# MAPLE_CDH_Periph.net
KiCad netlist of a schematic drawn in Altium Designer
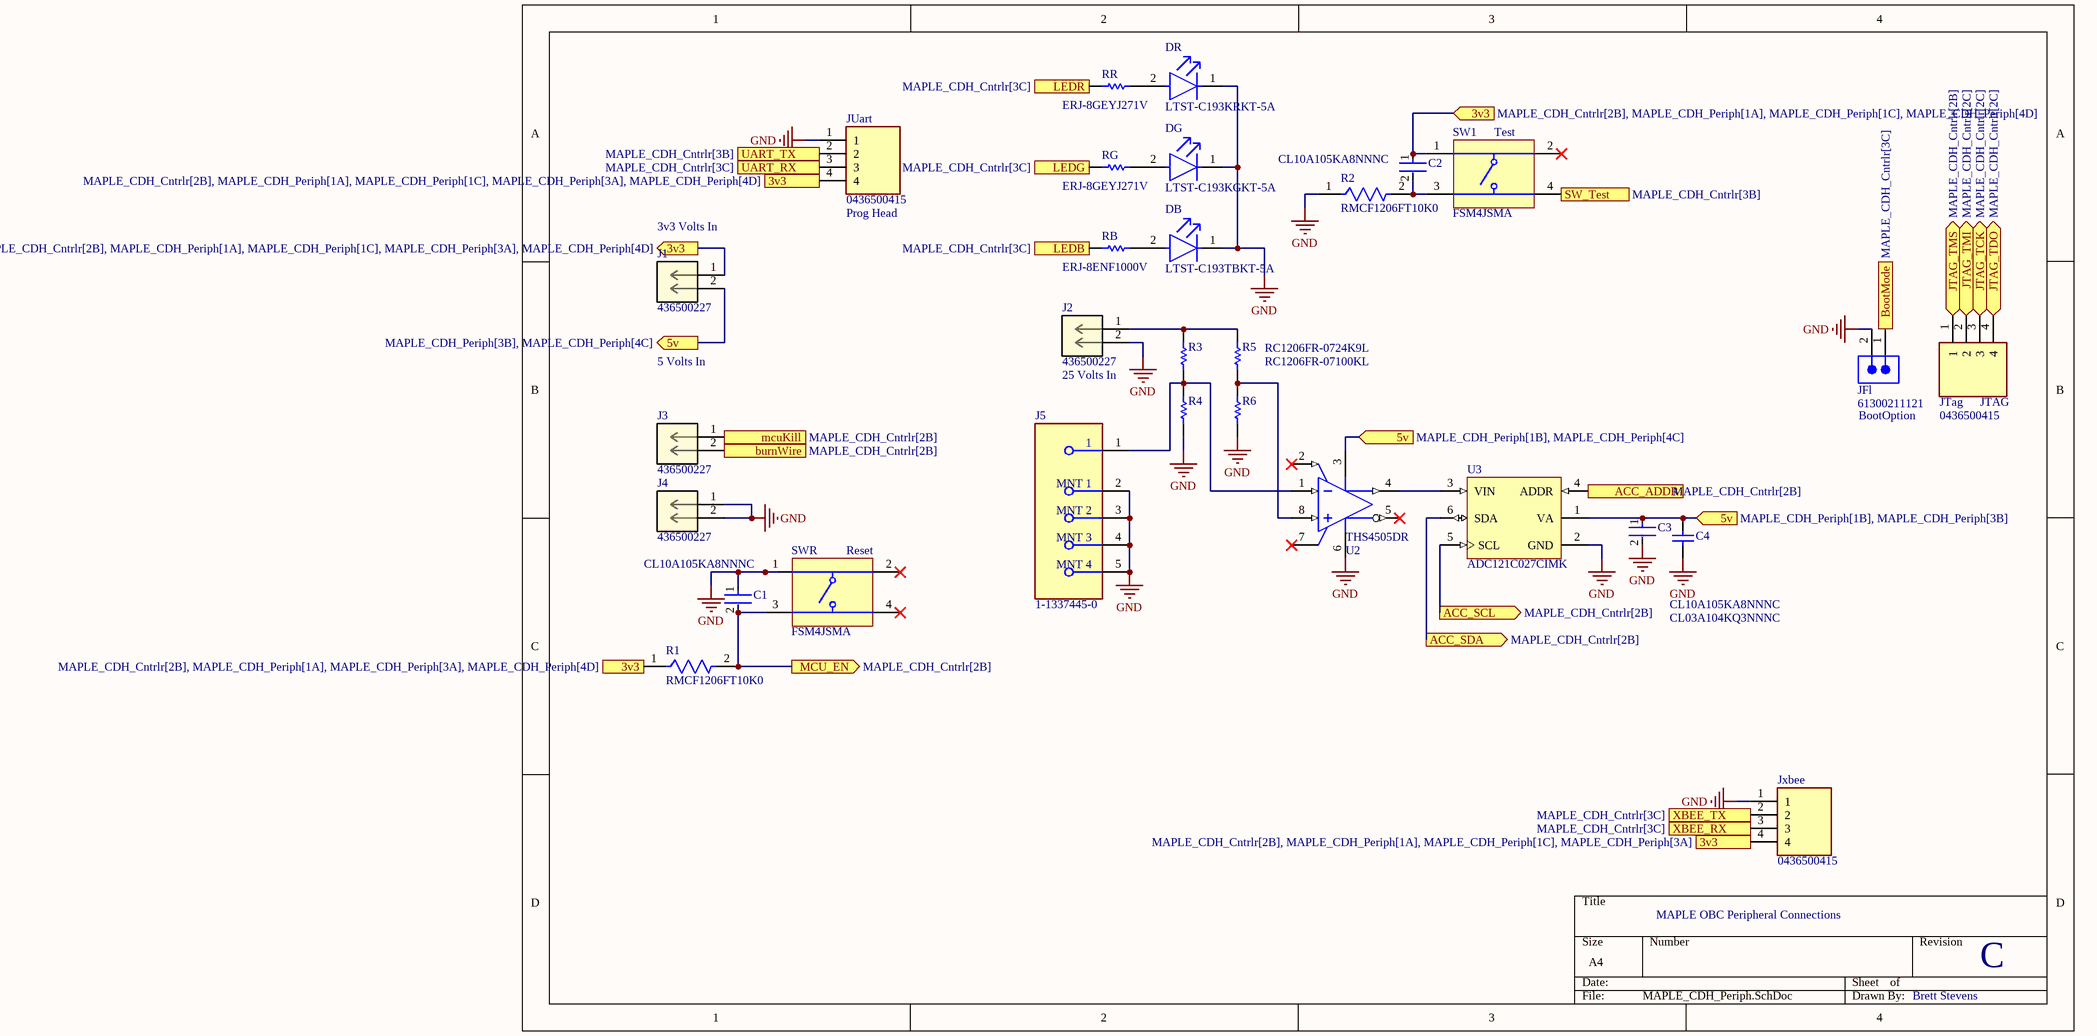
[diagram p0: MAPLE_CDH_Periph.SchDoc]

(export (version "E")
  (design (tool "Eeschema 10.0.6"))
  (components
    (comp (ref "C1")
      (value "CL10A105KA8NNNC")
      (footprint "FP-CL10-IPC_C")
      (description "Cap Ceramic 1uF 25V X5R ±10% Pad SMD 0603 +85°C T/R")
      (fields (field (name "VOLTAGE") "25V") (field (name "TOLERANCE") "10%"))
      (libsource (lib "Altium Content Vault") (part "b4654b650e69147ec39a6b967a45e02"))
    )
    (comp (ref "C2")
      (value "CL10A105KA8NNNC")
      (footprint "FP-CL10-IPC_C")
      (description "Cap Ceramic 1uF 25V X5R ±10% Pad SMD 0603 +85°C T/R")
      (fields (field (name "VOLTAGE") "25V") (field (name "TOLERANCE") "10%"))
      (libsource (lib "Altium Content Vault") (part "b4654b650e69147ec39a6b967a45e02"))
    )
    (comp (ref "C3")
      (value "CL10A105KA8NNNC")
      (footprint "FP-CL10-IPC_C")
      (description "Cap Ceramic 1uF 25V X5R ±10% Pad SMD 0603 +85°C T/R")
      (fields (field (name "VOLTAGE") "25V") (field (name "TOLERANCE") "10%"))
      (libsource (lib "Altium Content Vault") (part "b4654b650e69147ec39a6b967a45e02"))
    )
    (comp (ref "C4")
      (value "CL03A104KQ3NNNC")
      (footprint "CAPC0603X33X15ML03T05")
      (fields (field (name "MANUFACTURER") "Samsung"))
      (libsource (lib "Altium Content Vault") (part "CAP"))
    )
    (comp (ref "DB")
      (value "LTST-C193TBKT-5A")
      (footprint "FP-LTST-C193TBKT-5A-MFG")
      (description "LED BLUE CLEAR CHIP SMD")
      (libsource (lib "Altium Content Vault") (part "8706943c75ba83719d021d2fdc84c58"))
    )
    (comp (ref "DG")
      (value "LTST-C193KGKT-5A")
      (footprint "FP-LTST-C193KGKT-5A-MFG")
      (description "LED GREEN CLEAR CHIP SMD")
      (libsource (lib "Altium Content Vault") (part "8706943c75ba83719d021d2fdc84c58"))
    )
    (comp (ref "DR")
      (value "LTST-C193KRKT-5A")
      (footprint "FP-LTST-C193KRKT-5A-MFG")
      (description "LED RED CLEAR CHIP SMD")
      (libsource (lib "Altium Content Vault") (part "8706943c75ba83719d021d2fdc84c58"))
    )
    (comp (ref "J1")
      (value "436500227")
      (footprint "436500227:CON_436500227_MOL")
      (description "No Description Available")
      (fields (field (name "COPYRIGHT") "Copyright (C) 2023 Ultra Librarian. All rights reserved."))
      (libsource (lib "436500227") (part "436500227"))
    )
    (comp (ref "J2")
      (value "436500227")
      (footprint "436500227:CON_436500227_MOL")
      (description "No Description Available")
      (fields (field (name "COPYRIGHT") "Copyright (C) 2023 Ultra Librarian. All rights reserved."))
      (libsource (lib "436500227") (part "436500227"))
    )
    (comp (ref "J3")
      (value "436500227")
      (footprint "436500227:CON_436500227_MOL")
      (description "No Description Available")
      (fields (field (name "COPYRIGHT") "Copyright (C) 2023 Ultra Librarian. All rights reserved."))
      (libsource (lib "436500227") (part "436500227"))
    )
    (comp (ref "J4")
      (value "436500227")
      (footprint "436500227:CON_436500227_MOL")
      (description "No Description Available")
      (fields (field (name "COPYRIGHT") "Copyright (C) 2023 Ultra Librarian. All rights reserved."))
      (libsource (lib "436500227") (part "436500227"))
    )
    (comp (ref "J5")
      (value "1-1337445-0")
      (footprint "FP-1-1337445-0-MFG")
      (description "CONN BNC JACK STR 50 OHM PCB")
      (libsource (lib "Altium Content Vault") (part "c65b8a639cdaef1819ea20b5466f8fa"))
    )
    (comp (ref "JFl")
      (value "61300211121")
      (footprint "61300211121")
      (libsource (lib "Altium Content Vault") (part "Header_Male_1R_02P"))
    )
    (comp (ref "JTag")
      (value "0436500415")
      (footprint "MOLEX_0436500415")
      (description "Connector Header Through Hole 4 position 0.118 (3.00mm)")
      (fields (field (name "MF") "Molex"))
      (libsource (lib "") (part "0436500415_1"))
    )
    (comp (ref "JUart")
      (value "0436500415")
      (footprint "MOLEX_0436500415")
      (description "Connector Header Through Hole 4 position 0.118 (3.00mm)")
      (fields (field (name "MF") "Molex"))
      (libsource (lib "0436500415") (part "0436500415"))
    )
    (comp (ref "Jxbee")
      (value "0436500415")
      (footprint "MOLEX_0436500415")
      (description "Connector Header Through Hole 4 position 0.118 (3.00mm)")
      (fields (field (name "MF") "Molex"))
      (libsource (lib "0436500415") (part "0436500415"))
    )
    (comp (ref "R1")
      (value "RMCF1206FT10K0")
      (footprint "FP-RMCF1206-IPC_B")
      (description "10kΩ ±1% 0.25W 1206 Thick Film Chip Resistor AEC-Q200 compliant")
      (fields (field (name "TOLERANCE") "1%"))
      (libsource (lib "Altium Content Vault") (part "1029c3af85768c4190bb7ad29bc67b5"))
    )
    (comp (ref "R2")
      (value "RMCF1206FT10K0")
      (footprint "FP-RMCF1206-IPC_B")
      (description "10kΩ ±1% 0.25W 1206 Thick Film Chip Resistor AEC-Q200 compliant")
      (fields (field (name "TOLERANCE") "1%"))
      (libsource (lib "Altium Content Vault") (part "1029c3af85768c4190bb7ad29bc67b5"))
    )
    (comp (ref "R3")
      (value "~")
      (footprint "RESC3116X65X40NL10T20")
      (fields (field (name "MANUFACTURER") "Yageo") (field (name "PART NUMBER") "RC1206FR-0724K9L"))
      (libsource (lib "Altium Content Vault") (part "RES"))
    )
    (comp (ref "R4")
      (value "~")
      (footprint "RESC3116X65X40ML10T20")
      (description "Chip Resistor, 100 KOhm, +/- 1%, 0.25 W, -55 to 155 degC, 1206 (3216 Metric), RoHS, Tape and Reel")
      (fields (field (name "TOLERANCE") "1%") (field (name "MANUFACTURER") "Yageo"))
      (libsource (lib "Altium Content Vault") (part "RES-2"))
    )
    (comp (ref "R5")
      (value "RC1206FR-0724K9L")
      (footprint "RESC3116X65X40NL10T20")
      (fields (field (name "MANUFACTURER") "Yageo"))
      (libsource (lib "Altium Content Vault") (part "RES"))
    )
    (comp (ref "R6")
      (value "RC1206FR-07100KL")
      (footprint "RESC3116X65X40ML10T20")
      (description "Chip Resistor, 100 KOhm, +/- 1%, 0.25 W, -55 to 155 degC, 1206 (3216 Metric), RoHS, Tape and Reel")
      (fields (field (name "TOLERANCE") "1%") (field (name "MANUFACTURER") "Yageo"))
      (libsource (lib "Altium Content Vault") (part "RES-2"))
    )
    (comp (ref "RB")
      (value "ERJ-8ENF1000V")
      (footprint "RESC3216X70X50NL05T20")
      (fields (field (name "MANUFACTURER") "Panasonic"))
      (libsource (lib "Altium Content Vault") (part "RES"))
    )
    (comp (ref "RG")
      (value "ERJ-8GEYJ271V")
      (footprint "RESC3216X70X50NL05T20")
      (fields (field (name "MANUFACTURER") "Panasonic"))
      (libsource (lib "Altium Content Vault") (part "RES"))
    )
    (comp (ref "RR")
      (value "ERJ-8GEYJ271V")
      (footprint "RESC3216X70X50NL05T20")
      (fields (field (name "MANUFACTURER") "Panasonic"))
      (libsource (lib "Altium Content Vault") (part "RES"))
    )
    (comp (ref "SW1")
      (value "FSM4JSMA")
      (footprint "TECO-FSM4JSMA_V")
      (description "Swicth, SPST, 24 V, -35 to 85 degC, 4-Pin SMD, RoHS, Tape and Reel")
      (fields (field (name "MANUFACTURER") "TE Connectivity"))
      (libsource (lib "Altium Content Vault") (part "SW-SPST-4_A"))
    )
    (comp (ref "SWR")
      (value "FSM4JSMA")
      (footprint "TECO-FSM4JSMA_V")
      (description "Swicth, SPST, 24 V, -35 to 85 degC, 4-Pin SMD, RoHS, Tape and Reel")
      (fields (field (name "MANUFACTURER") "TE Connectivity"))
      (libsource (lib "Altium Content Vault") (part "SW-SPST-4_A"))
    )
    (comp (ref "U2")
      (value "THS4505DR")
      (footprint "D0008A_L")
      (fields (field (name "MANUFACTURER") "Texas Instruments"))
      (libsource (lib "Altium Content Vault") (part "TI-THS450XD_DGK8"))
    )
    (comp (ref "U3")
      (value "ADC121C027CIMK")
      (footprint "MK06A_N")
      (description "I2C-Compatible, 12-Bit Analog-to-Digital Converter with Alert Function, 6-pin Tiny SOT23")
      (fields (field (name "MANUFACTURER") "National Semiconductor"))
      (libsource (lib "Altium Content Vault") (part "CON-ADC-ADC101C027CIMK"))
    )
  )
  (nets
    (net (code "1") (name "/3v3") (class "Default")
      (node (ref "C2") (pin "1") (pinfunction "1_1") (pintype "passive"))
      (node (ref "J1") (pin "1") (pinfunction "1_1") (pintype "passive"))
      (node (ref "JUart") (pin "4") (pinfunction "4_4") (pintype "passive"))
      (node (ref "Jxbee") (pin "4") (pinfunction "4_4") (pintype "passive"))
      (node (ref "R1") (pin "1") (pinfunction "1_1") (pintype "passive"))
      (node (ref "SW1") (pin "1") (pinfunction "1_1") (pintype "passive"))
    )
    (net (code "2") (name "/5v") (class "Default")
      (node (ref "C3") (pin "1") (pinfunction "1_1") (pintype "passive"))
      (node (ref "C4") (pin "2") (pinfunction "2_2") (pintype "passive"))
      (node (ref "J1") (pin "2") (pinfunction "2_2") (pintype "passive"))
      (node (ref "U2") (pin "3") (pinfunction "VS+_3") (pintype "power_in"))
      (node (ref "U3") (pin "1") (pinfunction "VA_1") (pintype "power_in"))
    )
    (net (code "3") (name "/ACC_ADDR") (class "Default")
      (node (ref "U3") (pin "4") (pinfunction "ADDR_4") (pintype "input"))
    )
    (net (code "4") (name "/ACC_SCL") (class "Default")
      (node (ref "U3") (pin "5") (pinfunction "SCL_5") (pintype "input"))
    )
    (net (code "5") (name "/ACC_SDA") (class "Default")
      (node (ref "U3") (pin "6") (pinfunction "SDA_6") (pintype "bidirectional"))
    )
    (net (code "6") (name "/BootMode") (class "Default")
      (node (ref "JFl") (pin "1") (pinfunction "1_1") (pintype "passive"))
    )
    (net (code "7") (name "/JTAG_TCK") (class "Default")
      (node (ref "JTag") (pin "3") (pinfunction "3_3") (pintype "passive"))
    )
    (net (code "8") (name "/JTAG_TDO") (class "Default")
      (node (ref "JTag") (pin "4") (pinfunction "4_4") (pintype "passive"))
    )
    (net (code "9") (name "/JTAG_TMI") (class "Default")
      (node (ref "JTag") (pin "2") (pinfunction "2_2") (pintype "passive"))
    )
    (net (code "10") (name "/JTAG_TMS") (class "Default")
      (node (ref "JTag") (pin "1") (pinfunction "1_1") (pintype "passive"))
    )
    (net (code "11") (name "/LEDB") (class "Default")
      (node (ref "RB") (pin "1") (pinfunction "1_1") (pintype "passive"))
    )
    (net (code "12") (name "/LEDG") (class "Default")
      (node (ref "RG") (pin "1") (pinfunction "1_1") (pintype "passive"))
    )
    (net (code "13") (name "/LEDR") (class "Default")
      (node (ref "RR") (pin "1") (pinfunction "1_1") (pintype "passive"))
    )
    (net (code "14") (name "/MCU_EN") (class "Default")
      (node (ref "C1") (pin "2") (pinfunction "2_2") (pintype "passive"))
      (node (ref "R1") (pin "2") (pinfunction "2_2") (pintype "passive"))
      (node (ref "SWR") (pin "3") (pinfunction "3_3") (pintype "passive"))
    )
    (net (code "15") (name "/SW_Test") (class "Default")
      (node (ref "SW1") (pin "4") (pinfunction "4_4") (pintype "passive"))
    )
    (net (code "16") (name "/UART_RX") (class "Default")
      (node (ref "JUart") (pin "3") (pinfunction "3_3") (pintype "passive"))
    )
    (net (code "17") (name "/UART_TX") (class "Default")
      (node (ref "JUart") (pin "2") (pinfunction "2_2") (pintype "passive"))
    )
    (net (code "18") (name "/XBEE_RX") (class "Default")
      (node (ref "Jxbee") (pin "3") (pinfunction "3_3") (pintype "passive"))
    )
    (net (code "19") (name "/XBEE_TX") (class "Default")
      (node (ref "Jxbee") (pin "2") (pinfunction "2_2") (pintype "passive"))
    )
    (net (code "20") (name "/burnWire") (class "Default")
      (node (ref "J3") (pin "2") (pinfunction "2_2") (pintype "passive"))
    )
    (net (code "21") (name "/mcuKill") (class "Default")
      (node (ref "J3") (pin "1") (pinfunction "1_1") (pintype "passive"))
    )
    (net (code "22") (name "GND") (class "Default")
      (node (ref "C1") (pin "1") (pinfunction "1_1") (pintype "passive"))
      (node (ref "C3") (pin "2") (pinfunction "2_2") (pintype "passive"))
      (node (ref "C4") (pin "1") (pinfunction "1_1") (pintype "passive"))
      (node (ref "DB") (pin "1") (pinfunction "C_1") (pintype "passive"))
      (node (ref "DG") (pin "1") (pinfunction "C_1") (pintype "passive"))
      (node (ref "DR") (pin "1") (pinfunction "C_1") (pintype "passive"))
      (node (ref "J2") (pin "2") (pinfunction "2_2") (pintype "passive"))
      (node (ref "J4") (pin "1") (pinfunction "1_1") (pintype "passive"))
      (node (ref "J4") (pin "2") (pinfunction "2_2") (pintype "passive"))
      (node (ref "J5") (pin "2") (pinfunction "MNT_1_2") (pintype "passive"))
      (node (ref "J5") (pin "3") (pinfunction "MNT_2_3") (pintype "passive"))
      (node (ref "J5") (pin "4") (pinfunction "MNT_3_4") (pintype "passive"))
      (node (ref "J5") (pin "5") (pinfunction "MNT_4_5") (pintype "passive"))
      (node (ref "JFl") (pin "2") (pinfunction "2_2") (pintype "passive"))
      (node (ref "JUart") (pin "1") (pinfunction "1_1") (pintype "passive"))
      (node (ref "Jxbee") (pin "1") (pinfunction "1_1") (pintype "passive"))
      (node (ref "R2") (pin "1") (pinfunction "1_1") (pintype "passive"))
      (node (ref "R4") (pin "1") (pinfunction "1_1") (pintype "passive"))
      (node (ref "R6") (pin "1") (pinfunction "1_1") (pintype "passive"))
      (node (ref "SWR") (pin "1") (pinfunction "1_1") (pintype "passive"))
      (node (ref "U2") (pin "6") (pinfunction "VS-_6") (pintype "power_in"))
      (node (ref "U3") (pin "2") (pinfunction "GND_2") (pintype "power_in"))
    )
    (net (code "23") (name "Net-(C2-Pad2)") (class "Default")
      (node (ref "C2") (pin "2") (pinfunction "2_2") (pintype "passive"))
      (node (ref "R2") (pin "2") (pinfunction "2_2") (pintype "passive"))
      (node (ref "SW1") (pin "3") (pinfunction "3_3") (pintype "passive"))
    )
    (net (code "24") (name "Net-(DB-A)") (class "Default")
      (node (ref "DB") (pin "2") (pinfunction "A_2") (pintype "passive"))
      (node (ref "RB") (pin "2") (pinfunction "2_2") (pintype "passive"))
    )
    (net (code "25") (name "Net-(DG-A)") (class "Default")
      (node (ref "DG") (pin "2") (pinfunction "A_2") (pintype "passive"))
      (node (ref "RG") (pin "2") (pinfunction "2_2") (pintype "passive"))
    )
    (net (code "26") (name "Net-(DR-A)") (class "Default")
      (node (ref "DR") (pin "2") (pinfunction "A_2") (pintype "passive"))
      (node (ref "RR") (pin "2") (pinfunction "2_2") (pintype "passive"))
    )
    (net (code "27") (name "Net-(J2-Pad1)") (class "Default")
      (node (ref "J2") (pin "1") (pinfunction "1_1") (pintype "passive"))
      (node (ref "R3") (pin "2") (pinfunction "2_2") (pintype "passive"))
      (node (ref "R5") (pin "2") (pinfunction "2_2") (pintype "passive"))
    )
    (net (code "28") (name "Net-(U2-VIN+)") (class "Default")
      (node (ref "R5") (pin "1") (pinfunction "1_1") (pintype "passive"))
      (node (ref "R6") (pin "2") (pinfunction "2_2") (pintype "passive"))
      (node (ref "U2") (pin "8") (pinfunction "VIN+_8") (pintype "input"))
    )
    (net (code "29") (name "Net-(U2-VIN-)") (class "Default")
      (node (ref "J5") (pin "1") (pinfunction "1_1") (pintype "passive"))
      (node (ref "R3") (pin "1") (pinfunction "1_1") (pintype "passive"))
      (node (ref "R4") (pin "2") (pinfunction "2_2") (pintype "passive"))
      (node (ref "U2") (pin "1") (pinfunction "VIN-_1") (pintype "input"))
    )
    (net (code "30") (name "Net-(U2-VOUT+)") (class "Default")
      (node (ref "U2") (pin "4") (pinfunction "VOUT+_4") (pintype "output"))
      (node (ref "U3") (pin "3") (pinfunction "VIN_3") (pintype "input"))
    )
    (net (code "31") (name "unconnected-(SW1-Pad2)") (class "Default")
      (node (ref "SW1") (pin "2") (pinfunction "2_2") (pintype "passive+no_connect"))
    )
    (net (code "32") (name "unconnected-(SWR-Pad2)") (class "Default")
      (node (ref "SWR") (pin "2") (pinfunction "2_2") (pintype "passive+no_connect"))
    )
    (net (code "33") (name "unconnected-(SWR-Pad4)") (class "Default")
      (node (ref "SWR") (pin "4") (pinfunction "4_4") (pintype "passive+no_connect"))
    )
    (net (code "34") (name "unconnected-(U2-NC-Pad7)") (class "Default")
      (node (ref "U2") (pin "7") (pinfunction "NC_7") (pintype "passive+no_connect"))
    )
    (net (code "35") (name "unconnected-(U2-VOCM-Pad2)") (class "Default")
      (node (ref "U2") (pin "2") (pinfunction "VOCM_2") (pintype "input+no_connect"))
    )
    (net (code "36") (name "unconnected-(U2-VOUT--Pad5)") (class "Default")
      (node (ref "U2") (pin "5") (pinfunction "VOUT-_5") (pintype "output+no_connect"))
    )
  )
)
